# BHOnOfreSquareBoard.net
KiCad netlist of a schematic drawn in EAGLE
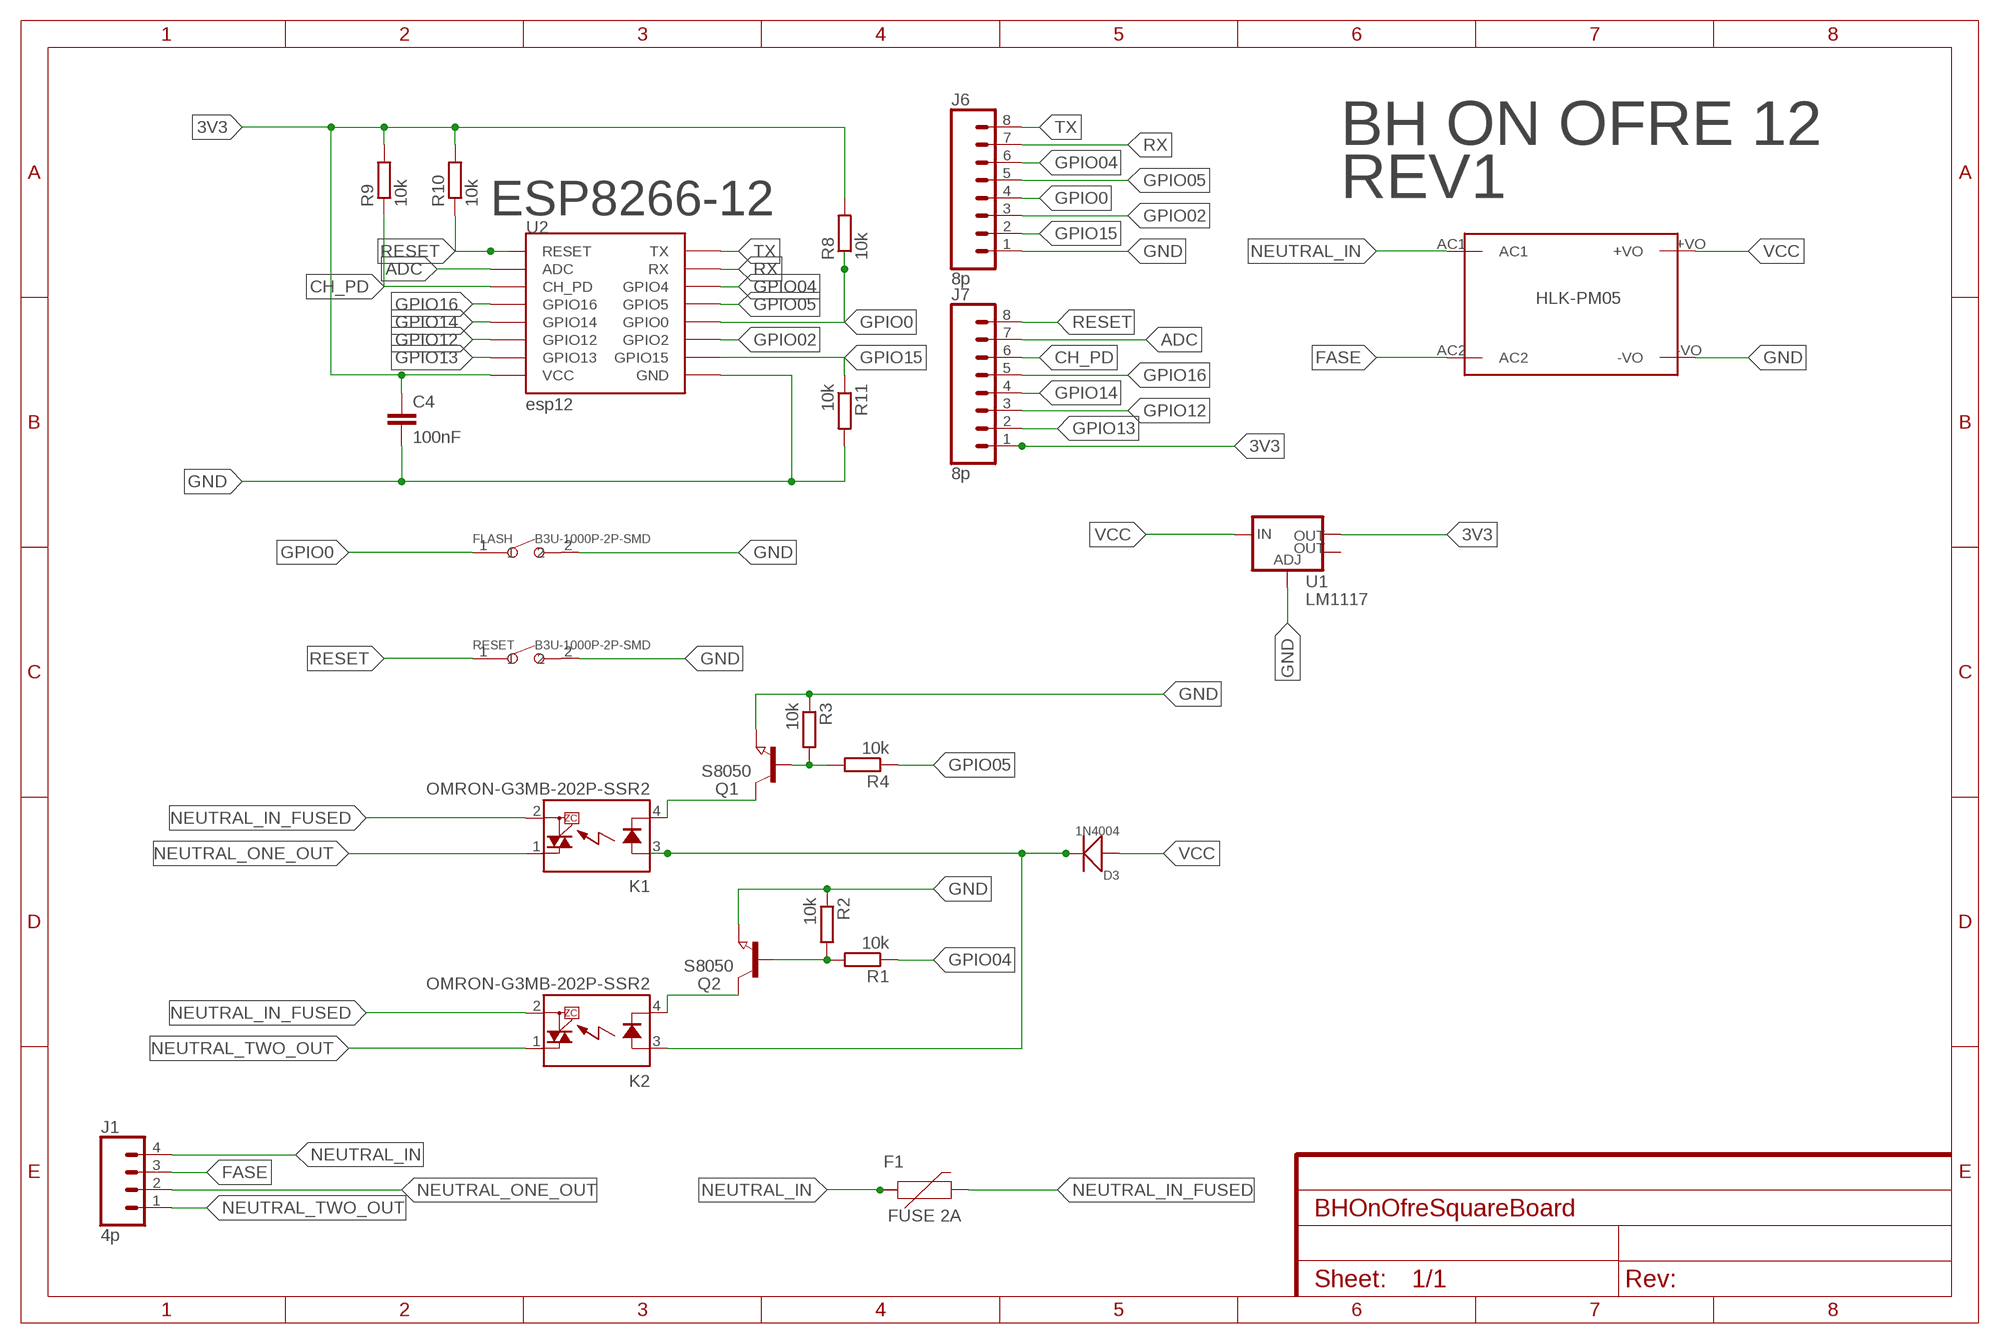
[diagram p0: schematic, sheet 1]

(export (version "E")
  (design (tool "Eeschema 10.0.6"))
  (components
    (comp (ref "C4")
      (value "100nF")
      (footprint "eagle-import:0603")
      (libsource (lib "eagle-import") (part "10NF-0603-50V-10%"))
    )
    (comp (ref "D3")
      (value "1N4004")
      (footprint "eagle-import:DO-214AC")
      (fields (field (name "MPN") "1N4007"))
      (libsource (lib "eagle-import") (part "DIODE-GEN-PURPOSE-1KV-1A(DO-214AC)"))
    )
    (comp (ref "F1")
      (value "FUSE 2A")
      (footprint "eagle-import:PTH")
      (libsource (lib "eagle-import") (part "PPTC_PTH"))
    )
    (comp (ref "FLASH")
      (value "B3U-1000P-2P-SMD")
      (footprint "eagle-import:SW2-2.6-3.0X2.5X1.2+0.4MM")
      (libsource (lib "eagle-import") (part "SMD-BUTTON(2P-3.0X2.5X1.2+0.4MM)-B3U-1000P-2P-SMD"))
    )
    (comp (ref "J1")
      (value "4p")
      (footprint "eagle-import:SCREWTERMINAL-3.5MM-4")
      (libsource (lib "eagle-import") (part "CONN_04SCREW"))
    )
    (comp (ref "J6")
      (value "8p")
      (footprint "eagle-import:1X08")
      (libsource (lib "eagle-import") (part "CONN_08{dblquote}"))
    )
    (comp (ref "J7")
      (value "8p")
      (footprint "eagle-import:1X08")
      (libsource (lib "eagle-import") (part "CONN_08{dblquote}"))
    )
    (comp (ref "K1")
      (value "OMRON-G3MB-202P-SSR2")
      (footprint "eagle-import:OMRON-G3MB-202P-SSR")
      (fields (field (name "MPN") "S202S02F"))
      (libsource (lib "eagle-import") (part "OMRON-G3MB-202P-SSR2"))
    )
    (comp (ref "K2")
      (value "OMRON-G3MB-202P-SSR2")
      (footprint "eagle-import:OMRON-G3MB-202P-SSR")
      (fields (field (name "MPN") "S202S02F"))
      (libsource (lib "eagle-import") (part "OMRON-G3MB-202P-SSR2"))
    )
    (comp (ref "Q1")
      (value "S8050")
      (footprint "eagle-import:SOT23")
      (libsource (lib "eagle-import") (part "NPN-TRANSISTOR_SOT23"))
    )
    (comp (ref "Q2")
      (value "S8050")
      (footprint "eagle-import:SOT23")
      (libsource (lib "eagle-import") (part "NPN-TRANSISTOR_SOT23"))
    )
    (comp (ref "R1")
      (value "10k")
      (footprint "eagle-import:R0603")
      (libsource (lib "eagle-import") (part "R-EU_R0603"))
    )
    (comp (ref "R2")
      (value "10k")
      (footprint "eagle-import:R0603")
      (libsource (lib "eagle-import") (part "R-EU_R0603"))
    )
    (comp (ref "R3")
      (value "10k")
      (footprint "eagle-import:R0603")
      (libsource (lib "eagle-import") (part "R-EU_R0603"))
    )
    (comp (ref "R4")
      (value "10k")
      (footprint "eagle-import:R0603")
      (libsource (lib "eagle-import") (part "R-EU_R0603"))
    )
    (comp (ref "R8")
      (value "10k")
      (footprint "eagle-import:R0603")
      (libsource (lib "eagle-import") (part "R-EU_R0603"))
    )
    (comp (ref "R9")
      (value "10k")
      (footprint "eagle-import:R0603")
      (libsource (lib "eagle-import") (part "R-EU_R0603"))
    )
    (comp (ref "R10")
      (value "10k")
      (footprint "eagle-import:R0603")
      (libsource (lib "eagle-import") (part "R-EU_R0603"))
    )
    (comp (ref "R11")
      (value "10k")
      (footprint "eagle-import:R0603")
      (libsource (lib "eagle-import") (part "R-EU_R0603"))
    )
    (comp (ref "RESET")
      (value "B3U-1000P-2P-SMD")
      (footprint "eagle-import:SW2-2.6-3.0X2.5X1.2+0.4MM")
      (libsource (lib "eagle-import") (part "SMD-BUTTON(2P-3.0X2.5X1.2+0.4MM)-B3U-1000P-2P-SMD"))
    )
    (comp (ref "U$2")
      (value "HLK-PM03")
      (footprint "eagle-import:HLK-PM03")
      (libsource (lib "eagle-import") (part "HLK-PM03"))
    )
    (comp (ref "U1")
      (value "LM1117")
      (footprint "eagle-import:SOT223")
      (libsource (lib "eagle-import") (part "V_REG_LM1117SOT223"))
    )
    (comp (ref "U2")
      (value "esp12")
      (footprint "eagle-import:ESP12-SMD")
      (libsource (lib "eagle-import") (part "ESP12SMD"))
    )
  )
  (nets
    (net (code "1") (name "3V3") (class "Default")
      (node (ref "C4") (pin "1") (pinfunction "1_1") (pintype "passive"))
      (node (ref "J7") (pin "1") (pinfunction "1_1") (pintype "passive"))
      (node (ref "R10") (pin "2") (pinfunction "2_2") (pintype "passive"))
      (node (ref "R8") (pin "2") (pinfunction "2_2") (pintype "passive"))
      (node (ref "R9") (pin "2") (pinfunction "2_2") (pintype "passive"))
      (node (ref "U1") (pin "2") (pinfunction "OUT_2") (pintype "output"))
      (node (ref "U2") (pin "VCC") (pinfunction "VCC_VCC") (pintype "bidirectional"))
    )
    (net (code "2") (name "ADC") (class "Default")
      (node (ref "J7") (pin "7") (pinfunction "7_7") (pintype "passive"))
      (node (ref "U2") (pin "ADC") (pinfunction "ADC_ADC") (pintype "bidirectional"))
    )
    (net (code "3") (name "CH_PD") (class "Default")
      (node (ref "J7") (pin "6") (pinfunction "6_6") (pintype "passive"))
      (node (ref "R9") (pin "1") (pinfunction "1_1") (pintype "passive"))
      (node (ref "U2") (pin "CH_PD") (pinfunction "CH_PD_CH_PD") (pintype "bidirectional"))
    )
    (net (code "4") (name "FASE") (class "Default")
      (node (ref "J1") (pin "3") (pinfunction "3_3") (pintype "passive"))
      (node (ref "U$2") (pin "AC2") (pinfunction "AC2_AC2") (pintype "bidirectional"))
    )
    (net (code "5") (name "GND") (class "Default")
      (node (ref "C4") (pin "2") (pinfunction "2_2") (pintype "passive"))
      (node (ref "FLASH") (pin "2") (pinfunction "2_2") (pintype "bidirectional"))
      (node (ref "J6") (pin "1") (pinfunction "1_1") (pintype "passive"))
      (node (ref "Q1") (pin "2") (pinfunction "E_2") (pintype "passive"))
      (node (ref "Q2") (pin "2") (pinfunction "E_2") (pintype "passive"))
      (node (ref "R11") (pin "2") (pinfunction "2_2") (pintype "passive"))
      (node (ref "R2") (pin "1") (pinfunction "1_1") (pintype "passive"))
      (node (ref "R3") (pin "1") (pinfunction "1_1") (pintype "passive"))
      (node (ref "RESET") (pin "2") (pinfunction "2_2") (pintype "bidirectional"))
      (node (ref "U$2") (pin "-VO") (pinfunction "-VO_-VO") (pintype "bidirectional"))
      (node (ref "U1") (pin "1") (pinfunction "ADJ_1") (pintype "input"))
      (node (ref "U2") (pin "GND") (pinfunction "GND_GND") (pintype "bidirectional"))
    )
    (net (code "6") (name "GPIO0") (class "Default")
      (node (ref "FLASH") (pin "1") (pinfunction "1_1") (pintype "bidirectional"))
      (node (ref "J6") (pin "4") (pinfunction "4_4") (pintype "passive"))
      (node (ref "R8") (pin "1") (pinfunction "1_1") (pintype "passive"))
      (node (ref "U2") (pin "GPIO0") (pinfunction "GPIO0_GPIO0") (pintype "bidirectional"))
    )
    (net (code "7") (name "GPIO02") (class "Default")
      (node (ref "J6") (pin "3") (pinfunction "3_3") (pintype "passive"))
      (node (ref "U2") (pin "GPIO2") (pinfunction "GPIO2_GPIO2") (pintype "bidirectional"))
    )
    (net (code "8") (name "GPIO04") (class "Default")
      (node (ref "J6") (pin "6") (pinfunction "6_6") (pintype "passive"))
      (node (ref "R1") (pin "1") (pinfunction "1_1") (pintype "passive"))
      (node (ref "U2") (pin "GPIO4") (pinfunction "GPIO4_GPIO4") (pintype "bidirectional"))
    )
    (net (code "9") (name "GPIO05") (class "Default")
      (node (ref "J6") (pin "5") (pinfunction "5_5") (pintype "passive"))
      (node (ref "R4") (pin "1") (pinfunction "1_1") (pintype "passive"))
      (node (ref "U2") (pin "GPIO5") (pinfunction "GPIO5_GPIO5") (pintype "bidirectional"))
    )
    (net (code "10") (name "GPIO12") (class "Default")
      (node (ref "J7") (pin "3") (pinfunction "3_3") (pintype "passive"))
      (node (ref "U2") (pin "GPIO12") (pinfunction "GPIO12_GPIO12") (pintype "bidirectional"))
    )
    (net (code "11") (name "GPIO13") (class "Default")
      (node (ref "J7") (pin "2") (pinfunction "2_2") (pintype "passive"))
      (node (ref "U2") (pin "GPIO13") (pinfunction "GPIO13_GPIO13") (pintype "bidirectional"))
    )
    (net (code "12") (name "GPIO14") (class "Default")
      (node (ref "J7") (pin "4") (pinfunction "4_4") (pintype "passive"))
      (node (ref "U2") (pin "GPIO14") (pinfunction "GPIO14_GPIO14") (pintype "bidirectional"))
    )
    (net (code "13") (name "GPIO15") (class "Default")
      (node (ref "J6") (pin "2") (pinfunction "2_2") (pintype "passive"))
      (node (ref "R11") (pin "1") (pinfunction "1_1") (pintype "passive"))
      (node (ref "U2") (pin "GPIO15") (pinfunction "GPIO15_GPIO15") (pintype "bidirectional"))
    )
    (net (code "14") (name "GPIO16") (class "Default")
      (node (ref "J7") (pin "5") (pinfunction "5_5") (pintype "passive"))
      (node (ref "U2") (pin "GPIO16") (pinfunction "GPIO16_GPIO16") (pintype "bidirectional"))
    )
    (net (code "15") (name "NEUTRAL_IN") (class "Default")
      (node (ref "F1") (pin "P$1") (pinfunction "1_P$1") (pintype "bidirectional"))
      (node (ref "J1") (pin "4") (pinfunction "4_4") (pintype "passive"))
      (node (ref "U$2") (pin "AC1") (pinfunction "AC1_AC1") (pintype "bidirectional"))
    )
    (net (code "16") (name "NEUTRAL_IN_FUSED") (class "Default")
      (node (ref "F1") (pin "P$2") (pinfunction "2_P$2") (pintype "bidirectional"))
      (node (ref "K1") (pin "2") (pinfunction "DS2_2") (pintype "passive"))
      (node (ref "K2") (pin "2") (pinfunction "DS2_2") (pintype "passive"))
    )
    (net (code "17") (name "NEUTRAL_ONE_OUT") (class "Default")
      (node (ref "J1") (pin "2") (pinfunction "2_2") (pintype "passive"))
      (node (ref "K1") (pin "1") (pinfunction "DS1_1") (pintype "passive"))
    )
    (net (code "18") (name "NEUTRAL_TWO_OUT") (class "Default")
      (node (ref "J1") (pin "1") (pinfunction "1_1") (pintype "passive"))
      (node (ref "K2") (pin "1") (pinfunction "DS1_1") (pintype "passive"))
    )
    (net (code "19") (name "Net-(D3--)") (class "Default")
      (node (ref "D3") (pin "2") (pinfunction "-_2") (pintype "passive"))
      (node (ref "K1") (pin "3") (pinfunction "A_3") (pintype "passive"))
      (node (ref "K2") (pin "3") (pinfunction "A_3") (pintype "passive"))
    )
    (net (code "20") (name "Net-(K1-K)") (class "Default")
      (node (ref "K1") (pin "4") (pinfunction "K_4") (pintype "passive"))
      (node (ref "Q1") (pin "3") (pinfunction "C_3") (pintype "passive"))
    )
    (net (code "21") (name "Net-(K2-K)") (class "Default")
      (node (ref "K2") (pin "4") (pinfunction "K_4") (pintype "passive"))
      (node (ref "Q2") (pin "3") (pinfunction "C_3") (pintype "passive"))
    )
    (net (code "22") (name "Net-(Q1-B)") (class "Default")
      (node (ref "Q1") (pin "1") (pinfunction "B_1") (pintype "passive"))
      (node (ref "R3") (pin "2") (pinfunction "2_2") (pintype "passive"))
      (node (ref "R4") (pin "2") (pinfunction "2_2") (pintype "passive"))
    )
    (net (code "23") (name "Net-(Q2-B)") (class "Default")
      (node (ref "Q2") (pin "1") (pinfunction "B_1") (pintype "passive"))
      (node (ref "R1") (pin "2") (pinfunction "2_2") (pintype "passive"))
      (node (ref "R2") (pin "2") (pinfunction "2_2") (pintype "passive"))
    )
    (net (code "24") (name "RESET") (class "Default")
      (node (ref "J7") (pin "8") (pinfunction "8_8") (pintype "passive"))
      (node (ref "R10") (pin "1") (pinfunction "1_1") (pintype "passive"))
      (node (ref "RESET") (pin "1") (pinfunction "1_1") (pintype "bidirectional"))
      (node (ref "U2") (pin "RESET") (pinfunction "RESET_RESET") (pintype "bidirectional"))
    )
    (net (code "25") (name "RX") (class "Default")
      (node (ref "J6") (pin "7") (pinfunction "7_7") (pintype "passive"))
      (node (ref "U2") (pin "RXD0") (pinfunction "RX_RXD0") (pintype "bidirectional"))
    )
    (net (code "26") (name "TX") (class "Default")
      (node (ref "J6") (pin "8") (pinfunction "8_8") (pintype "passive"))
      (node (ref "U2") (pin "TXD0") (pinfunction "TX_TXD0") (pintype "bidirectional"))
    )
    (net (code "27") (name "VCC") (class "Default")
      (node (ref "D3") (pin "1") (pinfunction "+_1") (pintype "passive"))
      (node (ref "U$2") (pin "+VO") (pinfunction "+VO_+VO") (pintype "bidirectional"))
      (node (ref "U1") (pin "3") (pinfunction "IN_3") (pintype "input"))
    )
    (net (code "28") (name "unconnected-(U1-OUT-Pad4)") (class "Default")
      (node (ref "U1") (pin "4") (pinfunction "OUT_4") (pintype "output"))
    )
  )
)
